# LM.net
KiCad netlist of a schematic drawn in EAGLE
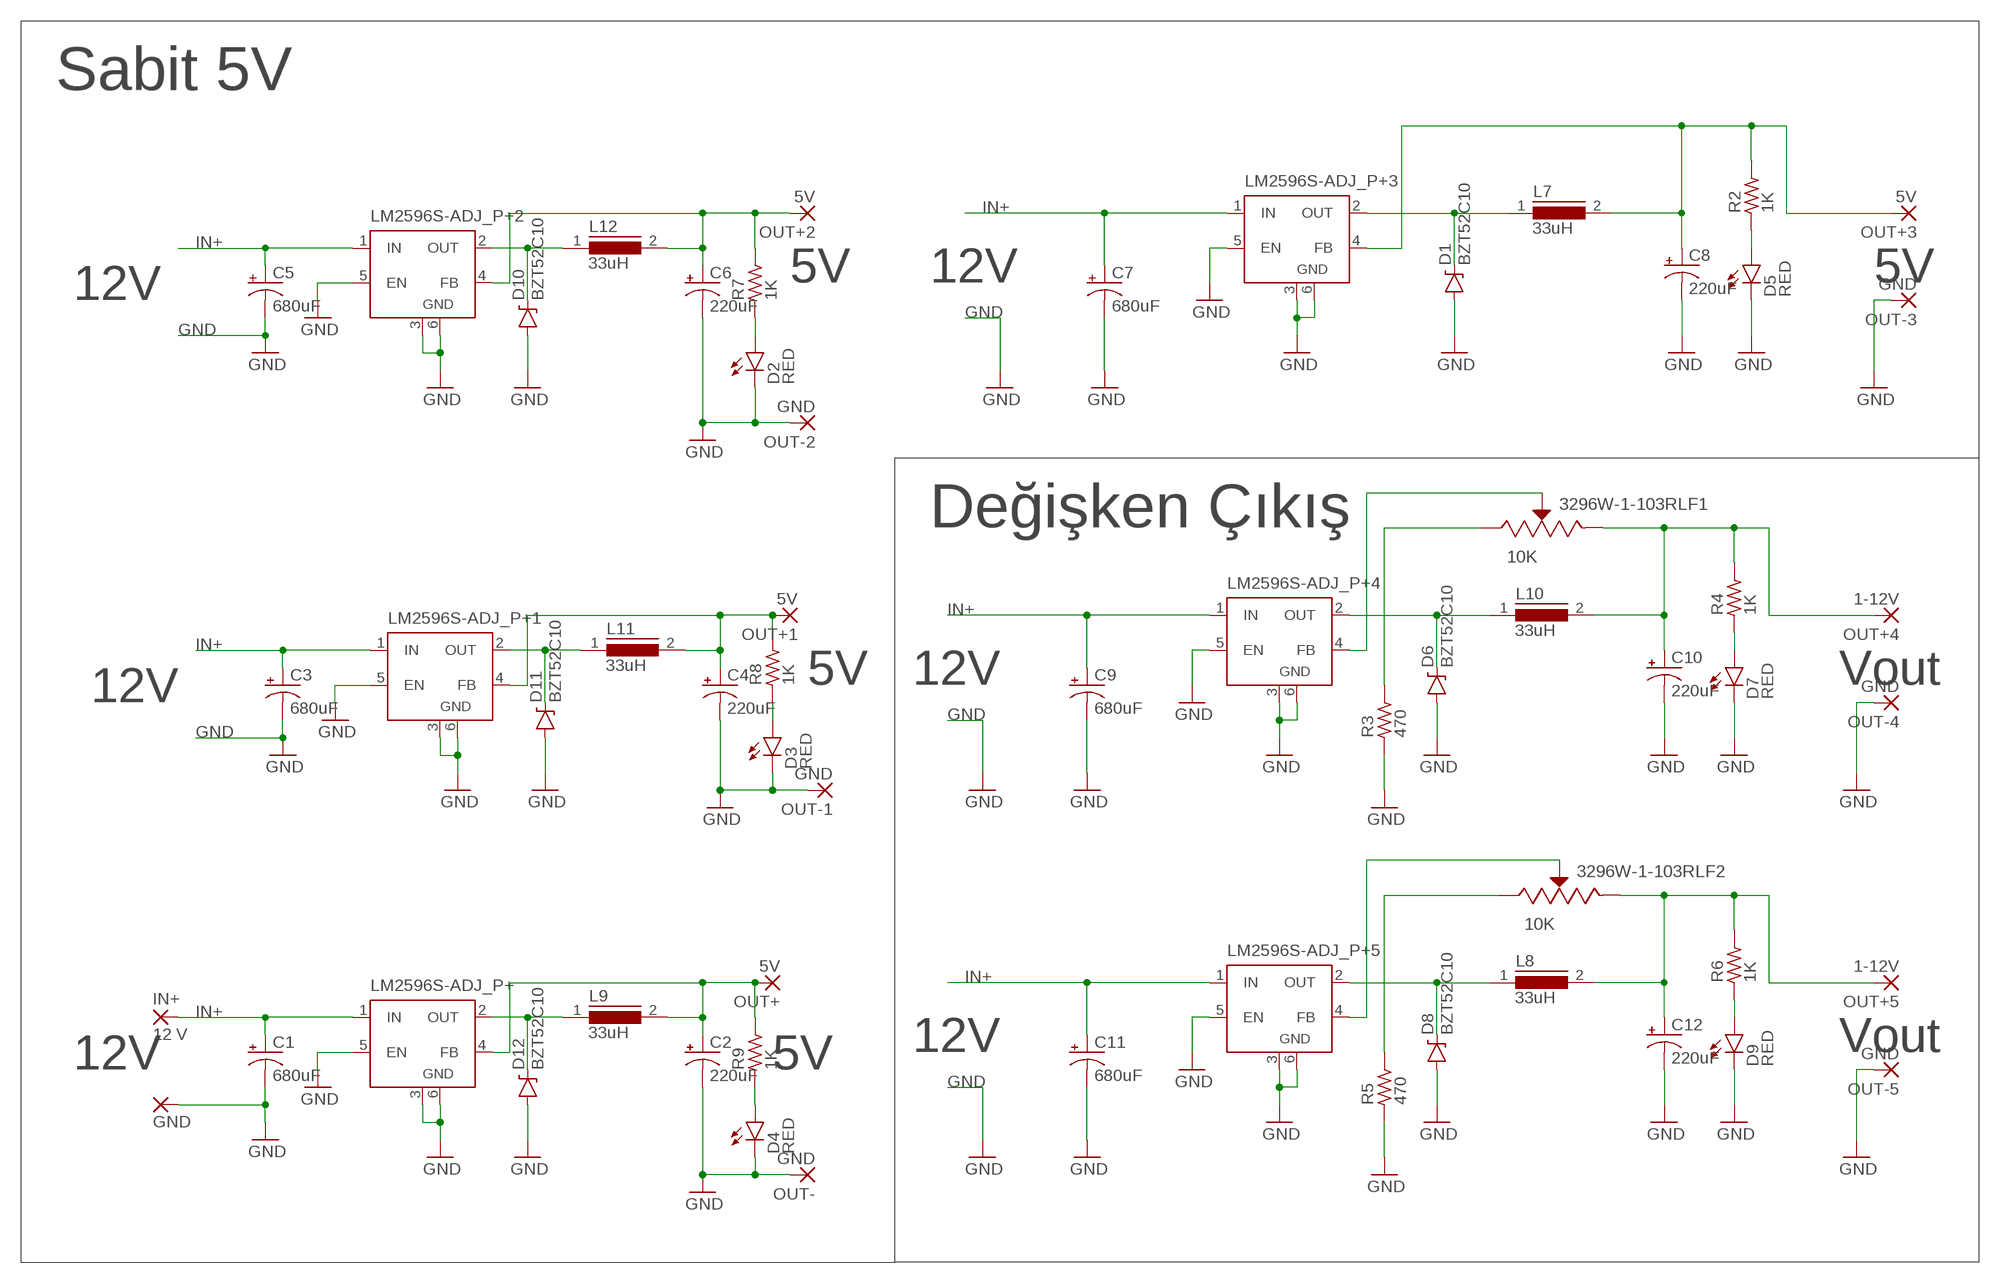
[diagram p0: schematic, sheet 1]

(export (version "E")
  (design (tool "Eeschema 10.0.6"))
  (components
    (comp (ref "3296W-1-103RLF1")
      (value "10K")
      (footprint "eagle-import:TRIM_3296W-1-103RLF")
      (fields (field (name "MF") "Bourns") (field (name "MP") "3296W-1-103RLF"))
      (libsource (lib "eagle-import") (part "3296W-1-103RLF"))
    )
    (comp (ref "3296W-1-103RLF2")
      (value "10K")
      (footprint "eagle-import:TRIM_3296W-1-103RLF")
      (fields (field (name "MF") "Bourns") (field (name "MP") "3296W-1-103RLF"))
      (libsource (lib "eagle-import") (part "3296W-1-103RLF"))
    )
    (comp (ref "C1")
      (value "680uF")
      (footprint "eagle-import:PANASONIC_G")
      (libsource (lib "eagle-import") (part "CAP_POLG"))
    )
    (comp (ref "C2")
      (value "220uF")
      (footprint "eagle-import:PANASONIC_G")
      (libsource (lib "eagle-import") (part "CAP_POLG"))
    )
    (comp (ref "C3")
      (value "680uF")
      (footprint "eagle-import:PANASONIC_G")
      (libsource (lib "eagle-import") (part "CAP_POLG"))
    )
    (comp (ref "C4")
      (value "220uF")
      (footprint "eagle-import:PANASONIC_G")
      (libsource (lib "eagle-import") (part "CAP_POLG"))
    )
    (comp (ref "C5")
      (value "680uF")
      (footprint "eagle-import:PANASONIC_G")
      (libsource (lib "eagle-import") (part "CAP_POLG"))
    )
    (comp (ref "C6")
      (value "220uF")
      (footprint "eagle-import:PANASONIC_G")
      (libsource (lib "eagle-import") (part "CAP_POLG"))
    )
    (comp (ref "C7")
      (value "680uF")
      (footprint "eagle-import:PANASONIC_G")
      (libsource (lib "eagle-import") (part "CAP_POLG"))
    )
    (comp (ref "C8")
      (value "220uF")
      (footprint "eagle-import:PANASONIC_G")
      (libsource (lib "eagle-import") (part "CAP_POLG"))
    )
    (comp (ref "C9")
      (value "680uF")
      (footprint "eagle-import:PANASONIC_G")
      (libsource (lib "eagle-import") (part "CAP_POLG"))
    )
    (comp (ref "C10")
      (value "220uF")
      (footprint "eagle-import:PANASONIC_G")
      (libsource (lib "eagle-import") (part "CAP_POLG"))
    )
    (comp (ref "C11")
      (value "680uF")
      (footprint "eagle-import:PANASONIC_G")
      (libsource (lib "eagle-import") (part "CAP_POLG"))
    )
    (comp (ref "C12")
      (value "220uF")
      (footprint "eagle-import:PANASONIC_G")
      (libsource (lib "eagle-import") (part "CAP_POLG"))
    )
    (comp (ref "D1")
      (value "BZT52C10")
      (footprint "eagle-import:SOD-123_2")
      (fields (field (name "MF") "Diotec Semiconductor"))
      (libsource (lib "eagle-import") (part "BZT52C10"))
    )
    (comp (ref "D2")
      (value "RED")
      (footprint "eagle-import:LED-1206")
      (libsource (lib "eagle-import") (part "LED-RED1206"))
    )
    (comp (ref "D3")
      (value "RED")
      (footprint "eagle-import:LED-1206")
      (libsource (lib "eagle-import") (part "LED-RED1206"))
    )
    (comp (ref "D4")
      (value "RED")
      (footprint "eagle-import:LED-1206")
      (libsource (lib "eagle-import") (part "LED-RED1206"))
    )
    (comp (ref "D5")
      (value "RED")
      (footprint "eagle-import:LED-1206")
      (libsource (lib "eagle-import") (part "LED-RED1206"))
    )
    (comp (ref "D6")
      (value "BZT52C10")
      (footprint "eagle-import:SOD-123_2")
      (fields (field (name "MF") "Diotec Semiconductor"))
      (libsource (lib "eagle-import") (part "BZT52C10"))
    )
    (comp (ref "D7")
      (value "RED")
      (footprint "eagle-import:LED-1206")
      (libsource (lib "eagle-import") (part "LED-RED1206"))
    )
    (comp (ref "D8")
      (value "BZT52C10")
      (footprint "eagle-import:SOD-123_2")
      (fields (field (name "MF") "Diotec Semiconductor"))
      (libsource (lib "eagle-import") (part "BZT52C10"))
    )
    (comp (ref "D9")
      (value "RED")
      (footprint "eagle-import:LED-1206")
      (libsource (lib "eagle-import") (part "LED-RED1206"))
    )
    (comp (ref "D10")
      (value "BZT52C10")
      (footprint "eagle-import:SOD-123_2")
      (fields (field (name "MF") "Diotec Semiconductor"))
      (libsource (lib "eagle-import") (part "BZT52C10"))
    )
    (comp (ref "D11")
      (value "BZT52C10")
      (footprint "eagle-import:SOD-123_2")
      (fields (field (name "MF") "Diotec Semiconductor"))
      (libsource (lib "eagle-import") (part "BZT52C10"))
    )
    (comp (ref "D12")
      (value "BZT52C10")
      (footprint "eagle-import:SOD-123_2")
      (fields (field (name "MF") "Diotec Semiconductor"))
      (libsource (lib "eagle-import") (part "BZT52C10"))
    )
    (comp (ref "IN+")
      (value "12 V")
      (footprint "eagle-import:SMD2,54-5,08")
      (libsource (lib "eagle-import") (part "SMD5"))
    )
    (comp (ref "IN-")
      (value "GND")
      (footprint "eagle-import:3,81_1,1")
      (libsource (lib "eagle-import") (part "3,81/1,1"))
    )
    (comp (ref "L7")
      (value "33uH")
      (footprint "eagle-import:DR127")
      (libsource (lib "eagle-import") (part "DR127"))
    )
    (comp (ref "L8")
      (value "33uH")
      (footprint "eagle-import:DR127")
      (libsource (lib "eagle-import") (part "DR127"))
    )
    (comp (ref "L9")
      (value "33uH")
      (footprint "eagle-import:DR127")
      (libsource (lib "eagle-import") (part "DR127"))
    )
    (comp (ref "L10")
      (value "33uH")
      (footprint "eagle-import:DR127")
      (libsource (lib "eagle-import") (part "DR127"))
    )
    (comp (ref "L11")
      (value "33uH")
      (footprint "eagle-import:DR127")
      (libsource (lib "eagle-import") (part "DR127"))
    )
    (comp (ref "L12")
      (value "33uH")
      (footprint "eagle-import:DR127")
      (libsource (lib "eagle-import") (part "DR127"))
    )
    (comp (ref "LM2596S-ADJ_P+")
      (value "LM2596S")
      (footprint "eagle-import:TO263-5")
      (libsource (lib "eagle-import") (part "LM2596S"))
    )
    (comp (ref "LM2596S-ADJ_P+1")
      (value "LM2596S")
      (footprint "eagle-import:TO263-5")
      (libsource (lib "eagle-import") (part "LM2596S"))
    )
    (comp (ref "LM2596S-ADJ_P+2")
      (value "LM2596S")
      (footprint "eagle-import:TO263-5")
      (libsource (lib "eagle-import") (part "LM2596S"))
    )
    (comp (ref "LM2596S-ADJ_P+3")
      (value "LM2596S")
      (footprint "eagle-import:TO263-5")
      (libsource (lib "eagle-import") (part "LM2596S"))
    )
    (comp (ref "LM2596S-ADJ_P+4")
      (value "LM2596S")
      (footprint "eagle-import:TO263-5")
      (libsource (lib "eagle-import") (part "LM2596S"))
    )
    (comp (ref "LM2596S-ADJ_P+5")
      (value "LM2596S")
      (footprint "eagle-import:TO263-5")
      (libsource (lib "eagle-import") (part "LM2596S"))
    )
    (comp (ref "OUT+")
      (value "5V")
      (footprint "eagle-import:SMD2,54-5,08")
      (libsource (lib "eagle-import") (part "SMD5"))
    )
    (comp (ref "OUT+1")
      (value "5V")
      (footprint "eagle-import:SMD2,54-5,08")
      (libsource (lib "eagle-import") (part "SMD5"))
    )
    (comp (ref "OUT+2")
      (value "5V")
      (footprint "eagle-import:SMD2,54-5,08")
      (libsource (lib "eagle-import") (part "SMD5"))
    )
    (comp (ref "OUT+3")
      (value "5V")
      (footprint "eagle-import:SMD2,54-5,08")
      (libsource (lib "eagle-import") (part "SMD5"))
    )
    (comp (ref "OUT+4")
      (value "1-12V")
      (footprint "eagle-import:SMD2,54-5,08")
      (libsource (lib "eagle-import") (part "SMD5"))
    )
    (comp (ref "OUT+5")
      (value "1-12V")
      (footprint "eagle-import:SMD2,54-5,08")
      (libsource (lib "eagle-import") (part "SMD5"))
    )
    (comp (ref "OUT-")
      (value "GND")
      (footprint "eagle-import:3,81_1,1")
      (libsource (lib "eagle-import") (part "3,81/1,1"))
    )
    (comp (ref "OUT-1")
      (value "GND")
      (footprint "eagle-import:3,81_1,1")
      (libsource (lib "eagle-import") (part "3,81/1,1"))
    )
    (comp (ref "OUT-2")
      (value "GND")
      (footprint "eagle-import:3,81_1,1")
      (libsource (lib "eagle-import") (part "3,81/1,1"))
    )
    (comp (ref "OUT-3")
      (value "GND")
      (footprint "eagle-import:3,81_1,1")
      (libsource (lib "eagle-import") (part "3,81/1,1"))
    )
    (comp (ref "OUT-4")
      (value "GND")
      (footprint "eagle-import:3,81_1,1")
      (libsource (lib "eagle-import") (part "3,81/1,1"))
    )
    (comp (ref "OUT-5")
      (value "GND")
      (footprint "eagle-import:3,81_1,1")
      (libsource (lib "eagle-import") (part "3,81/1,1"))
    )
    (comp (ref "R2")
      (value "1K")
      (footprint "eagle-import:R0805")
      (libsource (lib "eagle-import") (part "R_0805"))
    )
    (comp (ref "R3")
      (value "470")
      (footprint "eagle-import:R1206")
      (libsource (lib "eagle-import") (part "R_1206"))
    )
    (comp (ref "R4")
      (value "1K")
      (footprint "eagle-import:R0805")
      (libsource (lib "eagle-import") (part "R_0805"))
    )
    (comp (ref "R5")
      (value "470")
      (footprint "eagle-import:R1206")
      (libsource (lib "eagle-import") (part "R_1206"))
    )
    (comp (ref "R6")
      (value "1K")
      (footprint "eagle-import:R0805")
      (libsource (lib "eagle-import") (part "R_0805"))
    )
    (comp (ref "R7")
      (value "1K")
      (footprint "eagle-import:R0805")
      (libsource (lib "eagle-import") (part "R_0805"))
    )
    (comp (ref "R8")
      (value "1K")
      (footprint "eagle-import:R0805")
      (libsource (lib "eagle-import") (part "R_0805"))
    )
    (comp (ref "R9")
      (value "1K")
      (footprint "eagle-import:R0805")
      (libsource (lib "eagle-import") (part "R_0805"))
    )
  )
  (nets
    (net (code "1") (name "/IN+") (class "Default")
      (node (ref "C1") (pin "+") (pinfunction "+_+") (pintype "passive"))
      (node (ref "C11") (pin "+") (pinfunction "+_+") (pintype "passive"))
      (node (ref "C3") (pin "+") (pinfunction "+_+") (pintype "passive"))
      (node (ref "C5") (pin "+") (pinfunction "+_+") (pintype "passive"))
      (node (ref "C7") (pin "+") (pinfunction "+_+") (pintype "passive"))
      (node (ref "C9") (pin "+") (pinfunction "+_+") (pintype "passive"))
      (node (ref "IN+") (pin "1") (pinfunction "P_1") (pintype "passive"))
      (node (ref "LM2596S-ADJ_P+") (pin "1") (pinfunction "IN_1") (pintype "input"))
      (node (ref "LM2596S-ADJ_P+1") (pin "1") (pinfunction "IN_1") (pintype "input"))
      (node (ref "LM2596S-ADJ_P+2") (pin "1") (pinfunction "IN_1") (pintype "input"))
      (node (ref "LM2596S-ADJ_P+3") (pin "1") (pinfunction "IN_1") (pintype "input"))
      (node (ref "LM2596S-ADJ_P+4") (pin "1") (pinfunction "IN_1") (pintype "input"))
      (node (ref "LM2596S-ADJ_P+5") (pin "1") (pinfunction "IN_1") (pintype "input"))
    )
    (net (code "2") (name "GND") (class "Default")
      (node (ref "C1") (pin "-") (pinfunction "-_-") (pintype "passive"))
      (node (ref "C10") (pin "-") (pinfunction "-_-") (pintype "passive"))
      (node (ref "C11") (pin "-") (pinfunction "-_-") (pintype "passive"))
      (node (ref "C12") (pin "-") (pinfunction "-_-") (pintype "passive"))
      (node (ref "C2") (pin "-") (pinfunction "-_-") (pintype "passive"))
      (node (ref "C3") (pin "-") (pinfunction "-_-") (pintype "passive"))
      (node (ref "C4") (pin "-") (pinfunction "-_-") (pintype "passive"))
      (node (ref "C5") (pin "-") (pinfunction "-_-") (pintype "passive"))
      (node (ref "C6") (pin "-") (pinfunction "-_-") (pintype "passive"))
      (node (ref "C7") (pin "-") (pinfunction "-_-") (pintype "passive"))
      (node (ref "C8") (pin "-") (pinfunction "-_-") (pintype "passive"))
      (node (ref "C9") (pin "-") (pinfunction "-_-") (pintype "passive"))
      (node (ref "D1") (pin "A") (pinfunction "A_A") (pintype "passive"))
      (node (ref "D10") (pin "A") (pinfunction "A_A") (pintype "passive"))
      (node (ref "D11") (pin "A") (pinfunction "A_A") (pintype "passive"))
      (node (ref "D12") (pin "A") (pinfunction "A_A") (pintype "passive"))
      (node (ref "D2") (pin "C") (pinfunction "C_C") (pintype "passive"))
      (node (ref "D3") (pin "C") (pinfunction "C_C") (pintype "passive"))
      (node (ref "D4") (pin "C") (pinfunction "C_C") (pintype "passive"))
      (node (ref "D5") (pin "C") (pinfunction "C_C") (pintype "passive"))
      (node (ref "D6") (pin "A") (pinfunction "A_A") (pintype "passive"))
      (node (ref "D7") (pin "C") (pinfunction "C_C") (pintype "passive"))
      (node (ref "D8") (pin "A") (pinfunction "A_A") (pintype "passive"))
      (node (ref "D9") (pin "C") (pinfunction "C_C") (pintype "passive"))
      (node (ref "IN-") (pin "1") (pinfunction "P_1") (pintype "passive"))
      (node (ref "LM2596S-ADJ_P+") (pin "3") (pinfunction "GND_3") (pintype "power_in"))
      (node (ref "LM2596S-ADJ_P+") (pin "5") (pinfunction "EN_5") (pintype "input"))
      (node (ref "LM2596S-ADJ_P+") (pin "6") (pinfunction "GND_6") (pintype "power_in"))
      (node (ref "LM2596S-ADJ_P+1") (pin "3") (pinfunction "GND_3") (pintype "power_in"))
      (node (ref "LM2596S-ADJ_P+1") (pin "5") (pinfunction "EN_5") (pintype "input"))
      (node (ref "LM2596S-ADJ_P+1") (pin "6") (pinfunction "GND_6") (pintype "power_in"))
      (node (ref "LM2596S-ADJ_P+2") (pin "3") (pinfunction "GND_3") (pintype "power_in"))
      (node (ref "LM2596S-ADJ_P+2") (pin "5") (pinfunction "EN_5") (pintype "input"))
      (node (ref "LM2596S-ADJ_P+2") (pin "6") (pinfunction "GND_6") (pintype "power_in"))
      (node (ref "LM2596S-ADJ_P+3") (pin "3") (pinfunction "GND_3") (pintype "power_in"))
      (node (ref "LM2596S-ADJ_P+3") (pin "5") (pinfunction "EN_5") (pintype "input"))
      (node (ref "LM2596S-ADJ_P+3") (pin "6") (pinfunction "GND_6") (pintype "power_in"))
      (node (ref "LM2596S-ADJ_P+4") (pin "3") (pinfunction "GND_3") (pintype "power_in"))
      (node (ref "LM2596S-ADJ_P+4") (pin "5") (pinfunction "EN_5") (pintype "input"))
      (node (ref "LM2596S-ADJ_P+4") (pin "6") (pinfunction "GND_6") (pintype "power_in"))
      (node (ref "LM2596S-ADJ_P+5") (pin "3") (pinfunction "GND_3") (pintype "power_in"))
      (node (ref "LM2596S-ADJ_P+5") (pin "5") (pinfunction "EN_5") (pintype "input"))
      (node (ref "LM2596S-ADJ_P+5") (pin "6") (pinfunction "GND_6") (pintype "power_in"))
      (node (ref "OUT-") (pin "1") (pinfunction "P_1") (pintype "passive"))
      (node (ref "OUT-1") (pin "1") (pinfunction "P_1") (pintype "passive"))
      (node (ref "OUT-2") (pin "1") (pinfunction "P_1") (pintype "passive"))
      (node (ref "OUT-3") (pin "1") (pinfunction "P_1") (pintype "passive"))
      (node (ref "OUT-4") (pin "1") (pinfunction "P_1") (pintype "passive"))
      (node (ref "OUT-5") (pin "1") (pinfunction "P_1") (pintype "passive"))
      (node (ref "R3") (pin "1") (pinfunction "1_1") (pintype "passive"))
      (node (ref "R5") (pin "1") (pinfunction "1_1") (pintype "passive"))
    )
    (net (code "3") (name "Net-(3296W-1-103RLF1-CCW)") (class "Default")
      (node (ref "3296W-1-103RLF1") (pin "1") (pinfunction "CCW_1") (pintype "passive"))
      (node (ref "R3") (pin "2") (pinfunction "2_2") (pintype "passive"))
    )
    (net (code "4") (name "Net-(3296W-1-103RLF1-CW)") (class "Default")
      (node (ref "3296W-1-103RLF1") (pin "3") (pinfunction "CW_3") (pintype "passive"))
      (node (ref "C10") (pin "+") (pinfunction "+_+") (pintype "passive"))
      (node (ref "L10") (pin "2") (pinfunction "2_2") (pintype "passive"))
      (node (ref "OUT+4") (pin "1") (pinfunction "P_1") (pintype "passive"))
      (node (ref "R4") (pin "2") (pinfunction "2_2") (pintype "passive"))
    )
    (net (code "5") (name "Net-(3296W-1-103RLF1-WIPER)") (class "Default")
      (node (ref "3296W-1-103RLF1") (pin "2") (pinfunction "WIPER_2") (pintype "passive"))
      (node (ref "LM2596S-ADJ_P+4") (pin "4") (pinfunction "FB_4") (pintype "input"))
    )
    (net (code "6") (name "Net-(3296W-1-103RLF2-CCW)") (class "Default")
      (node (ref "3296W-1-103RLF2") (pin "1") (pinfunction "CCW_1") (pintype "passive"))
      (node (ref "R5") (pin "2") (pinfunction "2_2") (pintype "passive"))
    )
    (net (code "7") (name "Net-(3296W-1-103RLF2-CW)") (class "Default")
      (node (ref "3296W-1-103RLF2") (pin "3") (pinfunction "CW_3") (pintype "passive"))
      (node (ref "C12") (pin "+") (pinfunction "+_+") (pintype "passive"))
      (node (ref "L8") (pin "2") (pinfunction "2_2") (pintype "passive"))
      (node (ref "OUT+5") (pin "1") (pinfunction "P_1") (pintype "passive"))
      (node (ref "R6") (pin "2") (pinfunction "2_2") (pintype "passive"))
    )
    (net (code "8") (name "Net-(3296W-1-103RLF2-WIPER)") (class "Default")
      (node (ref "3296W-1-103RLF2") (pin "2") (pinfunction "WIPER_2") (pintype "passive"))
      (node (ref "LM2596S-ADJ_P+5") (pin "4") (pinfunction "FB_4") (pintype "input"))
    )
    (net (code "9") (name "Net-(D2-PadA)") (class "Default")
      (node (ref "D2") (pin "A") (pinfunction "A_A") (pintype "passive"))
      (node (ref "R7") (pin "1") (pinfunction "1_1") (pintype "passive"))
    )
    (net (code "10") (name "Net-(D3-PadA)") (class "Default")
      (node (ref "D3") (pin "A") (pinfunction "A_A") (pintype "passive"))
      (node (ref "R8") (pin "1") (pinfunction "1_1") (pintype "passive"))
    )
    (net (code "11") (name "Net-(D4-PadA)") (class "Default")
      (node (ref "D4") (pin "A") (pinfunction "A_A") (pintype "passive"))
      (node (ref "R9") (pin "1") (pinfunction "1_1") (pintype "passive"))
    )
    (net (code "12") (name "Net-(D5-PadA)") (class "Default")
      (node (ref "D5") (pin "A") (pinfunction "A_A") (pintype "passive"))
      (node (ref "R2") (pin "1") (pinfunction "1_1") (pintype "passive"))
    )
    (net (code "13") (name "Net-(D7-PadA)") (class "Default")
      (node (ref "D7") (pin "A") (pinfunction "A_A") (pintype "passive"))
      (node (ref "R4") (pin "1") (pinfunction "1_1") (pintype "passive"))
    )
    (net (code "14") (name "Net-(D9-PadA)") (class "Default")
      (node (ref "D9") (pin "A") (pinfunction "A_A") (pintype "passive"))
      (node (ref "R6") (pin "1") (pinfunction "1_1") (pintype "passive"))
    )
    (net (code "15") (name "Net-(LM2596S-ADJ_P+-FB)") (class "Default")
      (node (ref "C2") (pin "+") (pinfunction "+_+") (pintype "passive"))
      (node (ref "L9") (pin "2") (pinfunction "2_2") (pintype "passive"))
      (node (ref "LM2596S-ADJ_P+") (pin "4") (pinfunction "FB_4") (pintype "input"))
      (node (ref "OUT+") (pin "1") (pinfunction "P_1") (pintype "passive"))
      (node (ref "R9") (pin "2") (pinfunction "2_2") (pintype "passive"))
    )
    (net (code "16") (name "Net-(LM2596S-ADJ_P+-OUT)") (class "Default")
      (node (ref "D12") (pin "C") (pinfunction "C_C") (pintype "passive"))
      (node (ref "L9") (pin "1") (pinfunction "1_1") (pintype "passive"))
      (node (ref "LM2596S-ADJ_P+") (pin "2") (pinfunction "OUT_2") (pintype "output"))
    )
    (net (code "17") (name "Net-(LM2596S-ADJ_P+1-FB)") (class "Default")
      (node (ref "C4") (pin "+") (pinfunction "+_+") (pintype "passive"))
      (node (ref "L11") (pin "2") (pinfunction "2_2") (pintype "passive"))
      (node (ref "LM2596S-ADJ_P+1") (pin "4") (pinfunction "FB_4") (pintype "input"))
      (node (ref "OUT+1") (pin "1") (pinfunction "P_1") (pintype "passive"))
      (node (ref "R8") (pin "2") (pinfunction "2_2") (pintype "passive"))
    )
    (net (code "18") (name "Net-(LM2596S-ADJ_P+1-OUT)") (class "Default")
      (node (ref "D11") (pin "C") (pinfunction "C_C") (pintype "passive"))
      (node (ref "L11") (pin "1") (pinfunction "1_1") (pintype "passive"))
      (node (ref "LM2596S-ADJ_P+1") (pin "2") (pinfunction "OUT_2") (pintype "output"))
    )
    (net (code "19") (name "Net-(LM2596S-ADJ_P+2-FB)") (class "Default")
      (node (ref "C6") (pin "+") (pinfunction "+_+") (pintype "passive"))
      (node (ref "L12") (pin "2") (pinfunction "2_2") (pintype "passive"))
      (node (ref "LM2596S-ADJ_P+2") (pin "4") (pinfunction "FB_4") (pintype "input"))
      (node (ref "OUT+2") (pin "1") (pinfunction "P_1") (pintype "passive"))
      (node (ref "R7") (pin "2") (pinfunction "2_2") (pintype "passive"))
    )
    (net (code "20") (name "Net-(LM2596S-ADJ_P+2-OUT)") (class "Default")
      (node (ref "D10") (pin "C") (pinfunction "C_C") (pintype "passive"))
      (node (ref "L12") (pin "1") (pinfunction "1_1") (pintype "passive"))
      (node (ref "LM2596S-ADJ_P+2") (pin "2") (pinfunction "OUT_2") (pintype "output"))
    )
    (net (code "21") (name "Net-(LM2596S-ADJ_P+3-FB)") (class "Default")
      (node (ref "C8") (pin "+") (pinfunction "+_+") (pintype "passive"))
      (node (ref "L7") (pin "2") (pinfunction "2_2") (pintype "passive"))
      (node (ref "LM2596S-ADJ_P+3") (pin "4") (pinfunction "FB_4") (pintype "input"))
      (node (ref "OUT+3") (pin "1") (pinfunction "P_1") (pintype "passive"))
      (node (ref "R2") (pin "2") (pinfunction "2_2") (pintype "passive"))
    )
    (net (code "22") (name "Net-(LM2596S-ADJ_P+3-OUT)") (class "Default")
      (node (ref "D1") (pin "C") (pinfunction "C_C") (pintype "passive"))
      (node (ref "L7") (pin "1") (pinfunction "1_1") (pintype "passive"))
      (node (ref "LM2596S-ADJ_P+3") (pin "2") (pinfunction "OUT_2") (pintype "output"))
    )
    (net (code "23") (name "Net-(LM2596S-ADJ_P+4-OUT)") (class "Default")
      (node (ref "D6") (pin "C") (pinfunction "C_C") (pintype "passive"))
      (node (ref "L10") (pin "1") (pinfunction "1_1") (pintype "passive"))
      (node (ref "LM2596S-ADJ_P+4") (pin "2") (pinfunction "OUT_2") (pintype "output"))
    )
    (net (code "24") (name "Net-(LM2596S-ADJ_P+5-OUT)") (class "Default")
      (node (ref "D8") (pin "C") (pinfunction "C_C") (pintype "passive"))
      (node (ref "L8") (pin "1") (pinfunction "1_1") (pintype "passive"))
      (node (ref "LM2596S-ADJ_P+5") (pin "2") (pinfunction "OUT_2") (pintype "output"))
    )
  )
)
